# ST_LINK_V2-1.net
KiCad netlist of a schematic drawn in Altium Designer
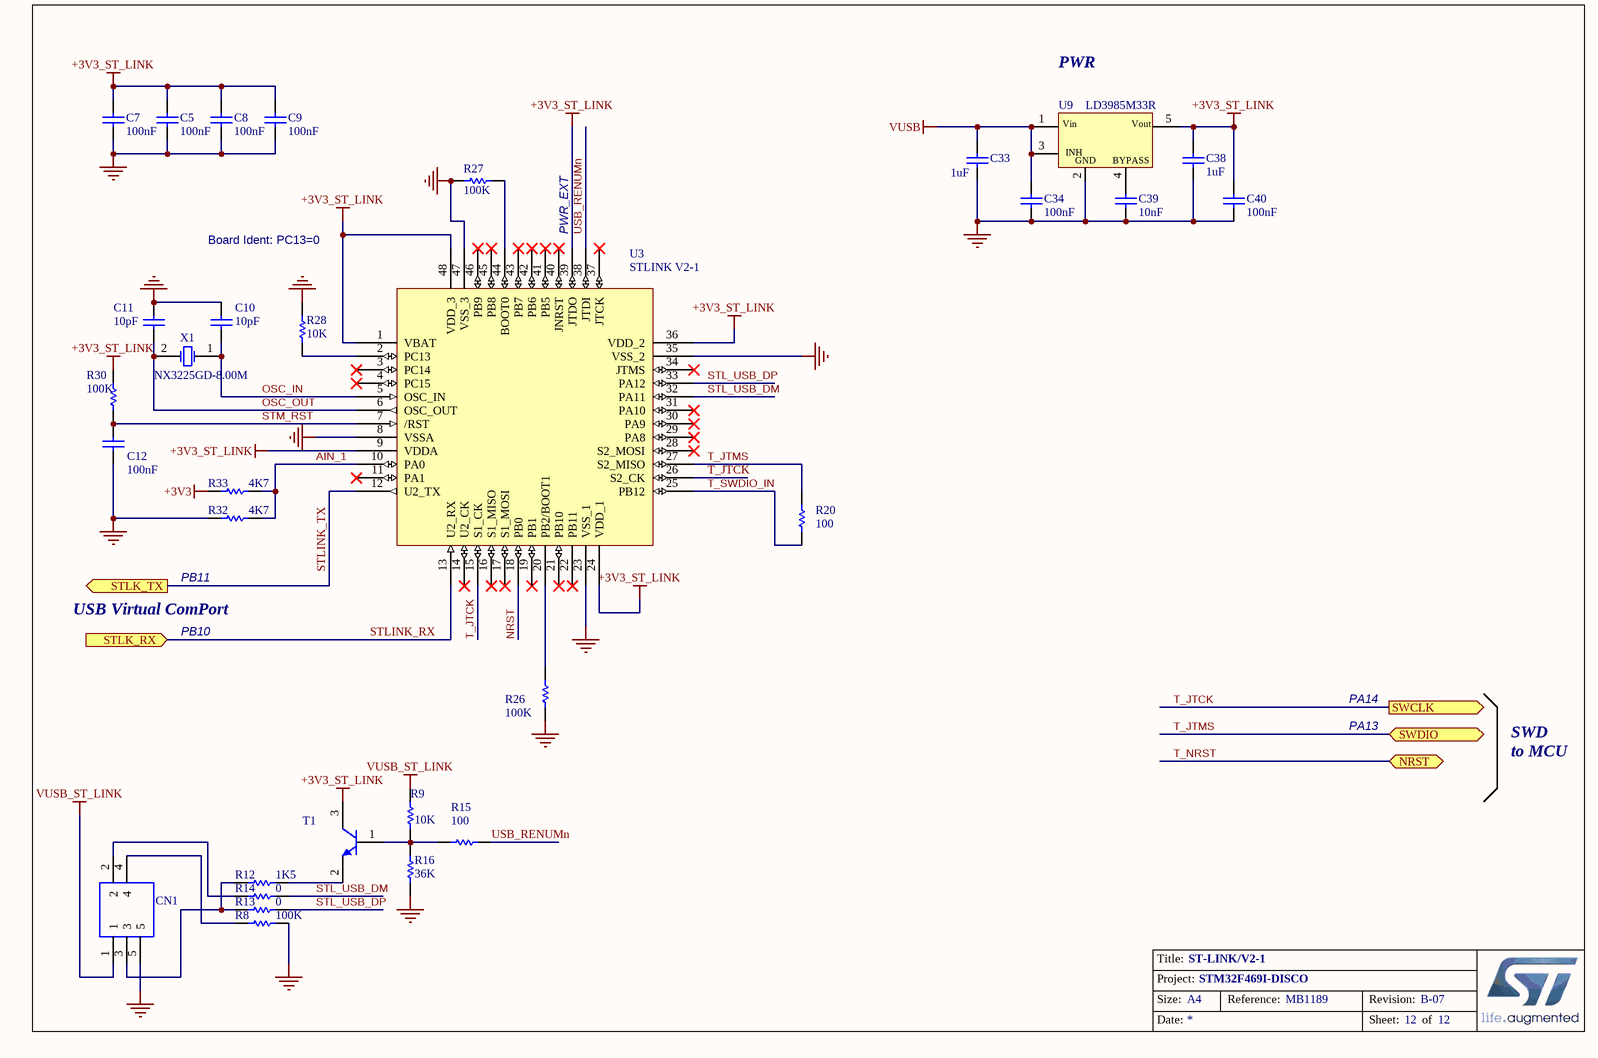
[diagram p0: ST_LINK_V2-1.SCHDOC]

(export (version "E")
  (design (tool "Eeschema 10.0.6"))
  (components
    (comp (ref "C5")
      (value "100nF")
      (footprint "CAP - 0603")
      (description "Capacitor 0402 / 0603 / 0805")
      (libsource (lib "MCD_TOOLS") (part "Capacitor_ST"))
    )
    (comp (ref "C7")
      (value "100nF")
      (footprint "CAP - 0603")
      (description "Capacitor 0402 / 0603 / 0805")
      (libsource (lib "MCD_TOOLS") (part "Capacitor_ST"))
    )
    (comp (ref "C8")
      (value "100nF")
      (footprint "CAP - 0603")
      (description "Capacitor 0402 / 0603 / 0805")
      (libsource (lib "MCD_TOOLS") (part "Capacitor_ST"))
    )
    (comp (ref "C9")
      (value "100nF")
      (footprint "CAP - 0603")
      (description "Capacitor 0402 / 0603 / 0805")
      (libsource (lib "MCD_TOOLS") (part "Capacitor_ST"))
    )
    (comp (ref "C10")
      (value "10pF")
      (footprint "CAP - 0603")
      (description "Capacitor 0402 / 0603 / 0805")
      (libsource (lib "MCD_TOOLS") (part "Capacitor_ST"))
    )
    (comp (ref "C11")
      (value "10pF")
      (footprint "CAP - 0603")
      (description "Capacitor 0402 / 0603 / 0805")
      (libsource (lib "MCD_TOOLS") (part "Capacitor_ST"))
    )
    (comp (ref "C12")
      (value "100nF")
      (footprint "CAP - 0603")
      (description "Capacitor 0402 / 0603 / 0805")
      (libsource (lib "MCD_TOOLS") (part "Capacitor_ST"))
    )
    (comp (ref "C33")
      (value "1uF")
      (footprint "CAP - 0402")
      (description "Capacitor")
      (fields (field (name "TOLERANCE") "10%"))
      (libsource (lib "MB963_1") (part "CAP SMD 0603  X5R 1µF 25V 10%"))
    )
    (comp (ref "C34")
      (value "100nF")
      (footprint "CAP - 0402")
      (description "Capacitor 0402 / 0603 / 0805")
      (libsource (lib "MCD_TOOLS") (part "Capacitor_ST"))
    )
    (comp (ref "C38")
      (value "1uF")
      (footprint "CAP - 0603")
      (description "Capacitor")
      (fields (field (name "TOLERANCE") "10%"))
      (libsource (lib "MB963_1") (part "CAP SMD 0603  X5R 1µF 25V 10%"))
    )
    (comp (ref "C39")
      (value "10nF")
      (footprint "CAP - 0603")
      (description "0603  X7R 10NF")
      (fields (field (name "TOLERANCE") "10%"))
      (libsource (lib "MB963_1") (part "CAP SMD 0603  X7R 10000PF 50V 10%"))
    )
    (comp (ref "C40")
      (value "100nF")
      (footprint "CAP - 0603")
      (description "Capacitor 0402 / 0603 / 0805")
      (libsource (lib "MCD_TOOLS") (part "Capacitor_ST"))
    )
    (comp (ref "CN1")
      (value "DX4R005HJ5R2000")
      (footprint "DX4R005HJ5")
      (description "USB Connectors microUSB 2.0 TYPE B STDMNT RCPT NO TAPER")
      (libsource (lib "DX4R005HJ5R2000") (part "DX4R005HJ5R2000"))
    )
    (comp (ref "R8")
      (value "100K")
      (footprint "RES - 0603")
      (description "Resistor")
      (fields (field (name "PUBLISHER") "Altium Limited"))
      (libsource (lib "Miscellaneous Devices") (part "res1"))
    )
    (comp (ref "R9")
      (value "10K")
      (footprint "RES - 0603")
      (description "Resistor")
      (fields (field (name "PUBLISHER") "Altium Limited"))
      (libsource (lib "") (part "Res1_1"))
    )
    (comp (ref "R12")
      (value "1K5")
      (footprint "RES - 0603")
      (description "Resistor")
      (libsource (lib "Miscellaneous Devices") (part "Res1"))
    )
    (comp (ref "R13")
      (value "0")
      (footprint "RES - 0603")
      (description "Resistor")
      (libsource (lib "Miscellaneous Devices") (part "Res1"))
    )
    (comp (ref "R14")
      (value "0")
      (footprint "RES - 0603")
      (description "Resistor")
      (libsource (lib "Miscellaneous Devices") (part "Res1"))
    )
    (comp (ref "R15")
      (value "100")
      (footprint "RES - 0603")
      (description "Resistor 0402 / 0603 / 0805")
      (libsource (lib "Miscellaneous Devices") (part "Res1"))
    )
    (comp (ref "R16")
      (value "36K")
      (footprint "RES - 0603")
      (description "Resistor")
      (fields (field (name "PUBLISHER") "Altium Limited"))
      (libsource (lib "") (part "Res1_1"))
    )
    (comp (ref "R20")
      (value "100")
      (footprint "RES - 0603")
      (description "Resistor")
      (libsource (lib "MCD_TOOLS") (part "Resistor_ST"))
    )
    (comp (ref "R26")
      (value "100K")
      (footprint "RES - 0603")
      (description "Resistor 0402 / 0603 / 0805")
      (libsource (lib "Miscellaneous Devices") (part "Res1"))
    )
    (comp (ref "R27")
      (value "100K")
      (footprint "RES - 0603")
      (description "Resistor 0402 / 0603 / 0805")
      (libsource (lib "Miscellaneous Devices") (part "Res1"))
    )
    (comp (ref "R28")
      (value "10K")
      (footprint "RES - 0603")
      (description "Resistor")
      (libsource (lib "Miscellaneous Devices") (part "Res1"))
    )
    (comp (ref "R30")
      (value "100K")
      (footprint "RES - 0603")
      (description "Resistor 0402 / 0603 / 0805")
      (libsource (lib "Miscellaneous Devices") (part "Res1"))
    )
    (comp (ref "R32")
      (value "4K7")
      (footprint "RES - 0603")
      (description "Resistor 0402 / 0603 / 0805")
      (libsource (lib "Miscellaneous Devices") (part "Res1"))
    )
    (comp (ref "R33")
      (value "4K7")
      (footprint "RES - 0603")
      (description "Resistor 0402 / 0603 / 0805")
      (libsource (lib "Miscellaneous Devices") (part "Res1"))
    )
    (comp (ref "T1")
      (value "9013 replaced by 2STR1160")
      (footprint "SOT23")
      (description "NPN Bipolar Transistor")
      (fields (field (name "PUBLISHER") "Altium Limited"))
      (libsource (lib "MB1167") (part "NPN"))
    )
    (comp (ref "U3")
      (value "STLINK V2-1")
      (footprint "QFP50P900X900X160-48N")
      (libsource (lib "*") (part "STM32F10x(48pin)"))
    )
    (comp (ref "U9")
      (value "LD3985M33R")
      (footprint "SOT95P280X145-5N")
      (description "Ultra low drop-low noise BiCMOS voltage, regulators low ESR capacitors compatible")
      (libsource (lib "MCD_TOOLS") (part "LD3985M33R"))
    )
    (comp (ref "X1")
      (value "NX3225GD-8.00M")
      (footprint "RESC3226X100N")
      (description "Crystal 8Mhz, 8pF, -+50PPM, SMD")
      (libsource (lib "MCD_TOOLS") (part "XTAL_8M_NX3225GD"))
    )
  )
  (nets
    (net (code "1") (name "+3V3") (class "Default")
      (node (ref "R33") (pin "1") (pinfunction "1_1") (pintype "passive"))
    )
    (net (code "2") (name "+3V3_ST_LINK") (class "Default")
      (node (ref "C38") (pin "1") (pinfunction "1_1") (pintype "passive"))
      (node (ref "C40") (pin "2") (pinfunction "2_2") (pintype "passive"))
      (node (ref "C5") (pin "2") (pinfunction "2_2") (pintype "passive"))
      (node (ref "C7") (pin "2") (pinfunction "2_2") (pintype "passive"))
      (node (ref "C8") (pin "2") (pinfunction "2_2") (pintype "passive"))
      (node (ref "C9") (pin "2") (pinfunction "2_2") (pintype "passive"))
      (node (ref "R30") (pin "2") (pinfunction "2_2") (pintype "passive"))
      (node (ref "T1") (pin "3") (pinfunction "C_3") (pintype "passive"))
      (node (ref "U3") (pin "1") (pinfunction "VBAT_1") (pintype "power_in"))
      (node (ref "U3") (pin "24") (pinfunction "VDD_1_24") (pintype "power_in"))
      (node (ref "U3") (pin "36") (pinfunction "VDD_2_36") (pintype "power_in"))
      (node (ref "U3") (pin "39") (pinfunction "JTDO_39") (pintype "bidirectional"))
      (node (ref "U3") (pin "48") (pinfunction "VDD_3_48") (pintype "power_in"))
      (node (ref "U3") (pin "9") (pinfunction "VDDA_9") (pintype "power_in"))
      (node (ref "U9") (pin "5") (pinfunction "Vout_5") (pintype "passive"))
    )
    (net (code "3") (name "/AIN_1") (class "Default")
      (node (ref "R32") (pin "2") (pinfunction "2_2") (pintype "passive"))
      (node (ref "R33") (pin "2") (pinfunction "2_2") (pintype "passive"))
      (node (ref "U3") (pin "10") (pinfunction "PA0_10") (pintype "bidirectional"))
    )
    (net (code "4") (name "/NRST") (class "Default")
      (node (ref "U3") (pin "18") (pinfunction "PB0_18") (pintype "bidirectional"))
    )
    (net (code "5") (name "/OSC_IN") (class "Default")
      (node (ref "C10") (pin "1") (pinfunction "1_1") (pintype "passive"))
      (node (ref "U3") (pin "5") (pinfunction "OSC_IN_5") (pintype "input"))
      (node (ref "X1") (pin "1") (pinfunction "OSC1_1") (pintype "passive"))
    )
    (net (code "6") (name "/OSC_OUT") (class "Default")
      (node (ref "C11") (pin "1") (pinfunction "1_1") (pintype "passive"))
      (node (ref "U3") (pin "6") (pinfunction "OSC_OUT_6") (pintype "output"))
      (node (ref "X1") (pin "2") (pinfunction "OSC2_2") (pintype "passive"))
    )
    (net (code "7") (name "/STLINK_RX") (class "Default")
      (node (ref "U3") (pin "13") (pinfunction "U2_RX_13") (pintype "input"))
    )
    (net (code "8") (name "/STLINK_TX") (class "Default")
      (node (ref "U3") (pin "12") (pinfunction "U2_TX_12") (pintype "output"))
    )
    (net (code "9") (name "/STL_USB_DM") (class "Default")
      (node (ref "R14") (pin "2") (pinfunction "2_2") (pintype "passive"))
      (node (ref "U3") (pin "32") (pinfunction "PA11_32") (pintype "bidirectional"))
    )
    (net (code "10") (name "/STL_USB_DP") (class "Default")
      (node (ref "R13") (pin "2") (pinfunction "2_2") (pintype "passive"))
      (node (ref "U3") (pin "33") (pinfunction "PA12_33") (pintype "bidirectional"))
    )
    (net (code "11") (name "/STM_RST") (class "Default")
      (node (ref "C12") (pin "2") (pinfunction "2_2") (pintype "passive"))
      (node (ref "R30") (pin "1") (pinfunction "1_1") (pintype "passive"))
      (node (ref "U3") (pin "7") (pinfunction "/RST_7") (pintype "input"))
    )
    (net (code "12") (name "/T_JTCK") (class "Default")
      (node (ref "U3") (pin "15") (pinfunction "S1_CK_15") (pintype "bidirectional"))
      (node (ref "U3") (pin "26") (pinfunction "S2_CK_26") (pintype "bidirectional"))
    )
    (net (code "13") (name "/T_JTMS") (class "Default")
      (node (ref "R20") (pin "2") (pinfunction "2_2") (pintype "passive"))
      (node (ref "U3") (pin "27") (pinfunction "S2_MISO_27") (pintype "bidirectional"))
    )
    (net (code "14") (name "/T_SWDIO_IN") (class "Default")
      (node (ref "R20") (pin "1") (pinfunction "1_1") (pintype "passive"))
      (node (ref "U3") (pin "25") (pinfunction "PB12_25") (pintype "bidirectional"))
    )
    (net (code "15") (name "/USB_RENUMn") (class "Default")
      (node (ref "R15") (pin "2") (pinfunction "2_2") (pintype "passive"))
      (node (ref "U3") (pin "38") (pinfunction "JTDI_38") (pintype "bidirectional"))
    )
    (net (code "16") (name "GND") (class "Default")
      (node (ref "C10") (pin "2") (pinfunction "2_2") (pintype "passive"))
      (node (ref "C11") (pin "2") (pinfunction "2_2") (pintype "passive"))
      (node (ref "C12") (pin "1") (pinfunction "1_1") (pintype "passive"))
      (node (ref "C33") (pin "1") (pinfunction "1_1") (pintype "passive"))
      (node (ref "C34") (pin "1") (pinfunction "1_1") (pintype "passive"))
      (node (ref "C38") (pin "2") (pinfunction "2_2") (pintype "passive"))
      (node (ref "C39") (pin "1") (pinfunction "1_1") (pintype "passive"))
      (node (ref "C40") (pin "1") (pinfunction "1_1") (pintype "passive"))
      (node (ref "C5") (pin "1") (pinfunction "1_1") (pintype "passive"))
      (node (ref "C7") (pin "1") (pinfunction "1_1") (pintype "passive"))
      (node (ref "C8") (pin "1") (pinfunction "1_1") (pintype "passive"))
      (node (ref "C9") (pin "1") (pinfunction "1_1") (pintype "passive"))
      (node (ref "CN1") (pin "5") (pinfunction "5_5") (pintype "passive"))
      (node (ref "R16") (pin "1") (pinfunction "1_1") (pintype "passive"))
      (node (ref "R26") (pin "1") (pinfunction "1_1") (pintype "passive"))
      (node (ref "R27") (pin "1") (pinfunction "1_1") (pintype "passive"))
      (node (ref "R28") (pin "1") (pinfunction "1_1") (pintype "passive"))
      (node (ref "R32") (pin "1") (pinfunction "1_1") (pintype "passive"))
      (node (ref "R8") (pin "2") (pinfunction "2_2") (pintype "passive"))
      (node (ref "U3") (pin "23") (pinfunction "VSS_1_23") (pintype "passive"))
      (node (ref "U3") (pin "35") (pinfunction "VSS_2_35") (pintype "passive"))
      (node (ref "U3") (pin "47") (pinfunction "VSS_3_47") (pintype "passive"))
      (node (ref "U3") (pin "8") (pinfunction "VSSA_8") (pintype "passive"))
      (node (ref "U9") (pin "2") (pinfunction "GND_2") (pintype "passive"))
    )
    (net (code "17") (name "Net-(CN1-Pad2)") (class "Default")
      (node (ref "CN1") (pin "2") (pinfunction "2_2") (pintype "passive"))
      (node (ref "R14") (pin "1") (pinfunction "1_1") (pintype "passive"))
    )
    (net (code "18") (name "Net-(CN1-Pad3)") (class "Default")
      (node (ref "CN1") (pin "3") (pinfunction "3_3") (pintype "passive"))
      (node (ref "R12") (pin "1") (pinfunction "1_1") (pintype "passive"))
      (node (ref "R13") (pin "1") (pinfunction "1_1") (pintype "passive"))
    )
    (net (code "19") (name "Net-(CN1-Pad4)") (class "Default")
      (node (ref "CN1") (pin "4") (pinfunction "4_4") (pintype "passive"))
      (node (ref "R8") (pin "1") (pinfunction "1_1") (pintype "passive"))
    )
    (net (code "20") (name "Net-(T1-B)") (class "Default")
      (node (ref "R15") (pin "1") (pinfunction "1_1") (pintype "passive"))
      (node (ref "R16") (pin "2") (pinfunction "2_2") (pintype "passive"))
      (node (ref "R9") (pin "1") (pinfunction "1_1") (pintype "passive"))
      (node (ref "T1") (pin "1") (pinfunction "B_1") (pintype "passive"))
    )
    (net (code "21") (name "Net-(T1-E)") (class "Default")
      (node (ref "R12") (pin "2") (pinfunction "2_2") (pintype "passive"))
      (node (ref "T1") (pin "2") (pinfunction "E_2") (pintype "passive"))
    )
    (net (code "22") (name "Net-(U3-BOOT0)") (class "Default")
      (node (ref "R27") (pin "2") (pinfunction "2_2") (pintype "passive"))
      (node (ref "U3") (pin "44") (pinfunction "BOOT0_44") (pintype "bidirectional"))
    )
    (net (code "23") (name "Net-(U3-PB2{slash}BOOT1)") (class "Default")
      (node (ref "R26") (pin "2") (pinfunction "2_2") (pintype "passive"))
      (node (ref "U3") (pin "20") (pinfunction "PB2/BOOT1_20") (pintype "passive"))
    )
    (net (code "24") (name "Net-(U3-PC13)") (class "Default")
      (node (ref "R28") (pin "2") (pinfunction "2_2") (pintype "passive"))
      (node (ref "U3") (pin "2") (pinfunction "PC13_2") (pintype "bidirectional"))
    )
    (net (code "25") (name "Net-(U9-BYPASS)") (class "Default")
      (node (ref "C39") (pin "2") (pinfunction "2_2") (pintype "passive"))
      (node (ref "U9") (pin "4") (pinfunction "BYPASS_4") (pintype "passive"))
    )
    (net (code "26") (name "VUSB") (class "Default")
      (node (ref "C33") (pin "2") (pinfunction "2_2") (pintype "passive"))
      (node (ref "C34") (pin "2") (pinfunction "2_2") (pintype "passive"))
      (node (ref "U9") (pin "1") (pinfunction "Vin_1") (pintype "passive"))
      (node (ref "U9") (pin "3") (pinfunction "CE_3") (pintype "passive"))
    )
    (net (code "27") (name "VUSB_ST_LINK") (class "Default")
      (node (ref "CN1") (pin "1") (pinfunction "1_1") (pintype "passive"))
      (node (ref "R9") (pin "2") (pinfunction "2_2") (pintype "passive"))
    )
    (net (code "28") (name "unconnected-(U3-JNRST-Pad40)") (class "Default")
      (node (ref "U3") (pin "40") (pinfunction "JNRST_40") (pintype "bidirectional+no_connect"))
    )
    (net (code "29") (name "unconnected-(U3-JTCK-Pad37)") (class "Default")
      (node (ref "U3") (pin "37") (pinfunction "JTCK_37") (pintype "bidirectional+no_connect"))
    )
    (net (code "30") (name "unconnected-(U3-JTMS-Pad34)") (class "Default")
      (node (ref "U3") (pin "34") (pinfunction "JTMS_34") (pintype "bidirectional+no_connect"))
    )
    (net (code "31") (name "unconnected-(U3-PA1-Pad11)") (class "Default")
      (node (ref "U3") (pin "11") (pinfunction "PA1_11") (pintype "bidirectional+no_connect"))
    )
    (net (code "32") (name "unconnected-(U3-PA8-Pad29)") (class "Default")
      (node (ref "U3") (pin "29") (pinfunction "PA8_29") (pintype "bidirectional+no_connect"))
    )
    (net (code "33") (name "unconnected-(U3-PA9-Pad30)") (class "Default")
      (node (ref "U3") (pin "30") (pinfunction "PA9_30") (pintype "bidirectional+no_connect"))
    )
    (net (code "34") (name "unconnected-(U3-PA10-Pad31)") (class "Default")
      (node (ref "U3") (pin "31") (pinfunction "PA10_31") (pintype "bidirectional+no_connect"))
    )
    (net (code "35") (name "unconnected-(U3-PB1-Pad19)") (class "Default")
      (node (ref "U3") (pin "19") (pinfunction "PB1_19") (pintype "bidirectional+no_connect"))
    )
    (net (code "36") (name "unconnected-(U3-PB5-Pad41)") (class "Default")
      (node (ref "U3") (pin "41") (pinfunction "PB5_41") (pintype "bidirectional+no_connect"))
    )
    (net (code "37") (name "unconnected-(U3-PB6-Pad42)") (class "Default")
      (node (ref "U3") (pin "42") (pinfunction "PB6_42") (pintype "bidirectional+no_connect"))
    )
    (net (code "38") (name "unconnected-(U3-PB7-Pad43)") (class "Default")
      (node (ref "U3") (pin "43") (pinfunction "PB7_43") (pintype "bidirectional+no_connect"))
    )
    (net (code "39") (name "unconnected-(U3-PB8-Pad45)") (class "Default")
      (node (ref "U3") (pin "45") (pinfunction "PB8_45") (pintype "bidirectional+no_connect"))
    )
    (net (code "40") (name "unconnected-(U3-PB9-Pad46)") (class "Default")
      (node (ref "U3") (pin "46") (pinfunction "PB9_46") (pintype "bidirectional+no_connect"))
    )
    (net (code "41") (name "unconnected-(U3-PB10-Pad21)") (class "Default")
      (node (ref "U3") (pin "21") (pinfunction "PB10_21") (pintype "bidirectional+no_connect"))
    )
    (net (code "42") (name "unconnected-(U3-PB11-Pad22)") (class "Default")
      (node (ref "U3") (pin "22") (pinfunction "PB11_22") (pintype "passive+no_connect"))
    )
    (net (code "43") (name "unconnected-(U3-PC14-Pad3)") (class "Default")
      (node (ref "U3") (pin "3") (pinfunction "PC14_3") (pintype "bidirectional+no_connect"))
    )
    (net (code "44") (name "unconnected-(U3-PC15-Pad4)") (class "Default")
      (node (ref "U3") (pin "4") (pinfunction "PC15_4") (pintype "bidirectional+no_connect"))
    )
    (net (code "45") (name "unconnected-(U3-S1_MISO-Pad16)") (class "Default")
      (node (ref "U3") (pin "16") (pinfunction "S1_MISO_16") (pintype "bidirectional+no_connect"))
    )
    (net (code "46") (name "unconnected-(U3-S1_MOSI-Pad17)") (class "Default")
      (node (ref "U3") (pin "17") (pinfunction "S1_MOSI_17") (pintype "bidirectional+no_connect"))
    )
    (net (code "47") (name "unconnected-(U3-S2_MOSI-Pad28)") (class "Default")
      (node (ref "U3") (pin "28") (pinfunction "S2_MOSI_28") (pintype "bidirectional+no_connect"))
    )
    (net (code "48") (name "unconnected-(U3-U2_CK-Pad14)") (class "Default")
      (node (ref "U3") (pin "14") (pinfunction "U2_CK_14") (pintype "bidirectional+no_connect"))
    )
  )
)
